# Power.net
KiCad netlist of a schematic drawn in Altium Designer
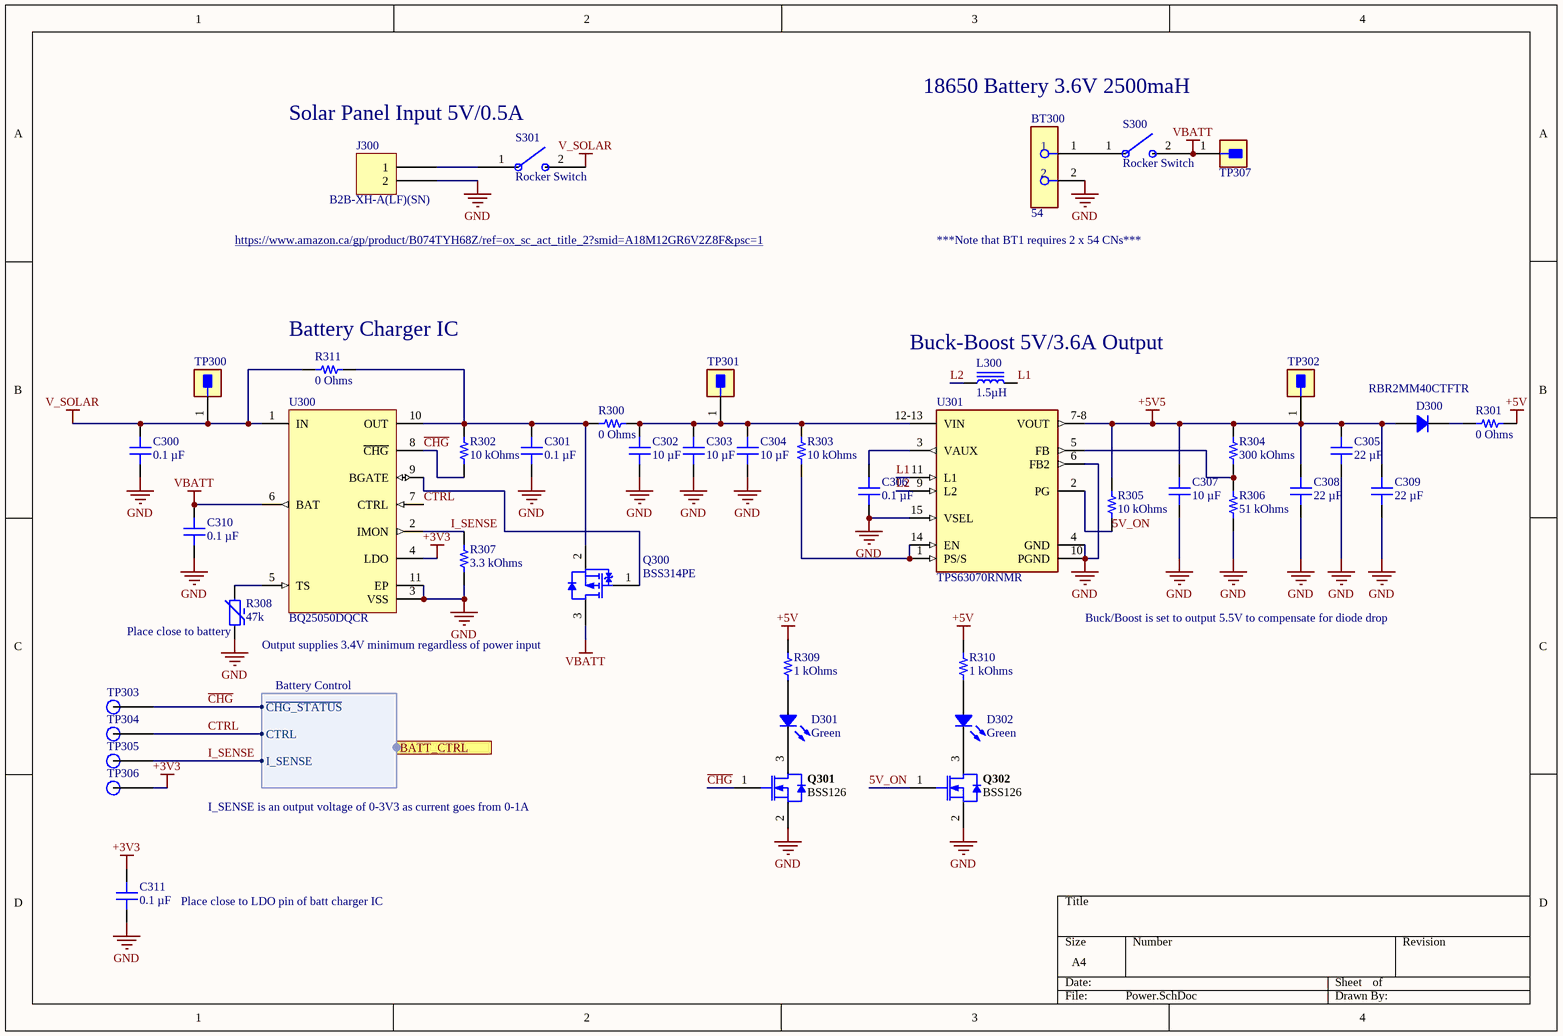
[diagram p0: Power.SchDoc]

(export (version "E")
  (design (tool "Eeschema 10.0.6"))
  (components
    (comp (ref "BT300")
      (value "54")
      (footprint "FP-54-MFG")
      (description "Cylindrical Battery Contacts, Clips, Holders & Springs 16-19mm PC BATTERY CLIP")
      (libsource (lib "Americas- Environmental Engineering Club- University of Victoria") (part "98815daf2f2c152b0c43f5ab9800df6"))
    )
    (comp (ref "C300")
      (value "0.1 µF")
      (footprint "CAP 0603_1608")
      (description "CAP CER 0.1UF 50V X7R 0603")
      (fields (field (name "PART NUMBER") "C0603C104K5RAC7411") (field (name "MANUFACTURER") "KEMET"))
      (libsource (lib "Celestial Altium Library - altium_library") (part "Capacitor"))
    )
    (comp (ref "C301")
      (value "0.1 µF")
      (footprint "CAP 0603_1608")
      (description "CAP CER 0.1UF 50V X7R 0603")
      (fields (field (name "PART NUMBER") "C0603C104K5RAC7411") (field (name "MANUFACTURER") "KEMET"))
      (libsource (lib "Celestial Altium Library - altium_library") (part "Capacitor"))
    )
    (comp (ref "C302")
      (value "10 µF")
      (footprint "CAP 0603_1608")
      (description "CAP CER 10UF 25V X5R 0603")
      (fields
        (field (name "PART NUMBER") "GRM188R61E106MA73J")
        (field (name "MANUFACTURER") "Murata Electronics")
      )
      (libsource (lib "Celestial Altium Library - altium_library") (part "Capacitor"))
    )
    (comp (ref "C303")
      (value "10 µF")
      (footprint "CAP 0603_1608")
      (description "CAP CER 10UF 25V X5R 0603")
      (fields
        (field (name "PART NUMBER") "GRM188R61E106MA73J")
        (field (name "MANUFACTURER") "Murata Electronics")
      )
      (libsource (lib "Celestial Altium Library - altium_library") (part "Capacitor"))
    )
    (comp (ref "C304")
      (value "10 µF")
      (footprint "CAP 0603_1608")
      (description "CAP CER 10UF 25V X5R 0603")
      (fields
        (field (name "PART NUMBER") "GRM188R61E106MA73J")
        (field (name "MANUFACTURER") "Murata Electronics")
      )
      (libsource (lib "Celestial Altium Library - altium_library") (part "Capacitor"))
    )
    (comp (ref "C305")
      (value "22 µF")
      (footprint "CAP 0805_2012")
      (description "CAP CER 22UF 16V X5R 0805")
      (fields
        (field (name "PART NUMBER") "CL21A226MOQNNNE")
        (field (name "MANUFACTURER") "Samsung Electro-Mechanics")
      )
      (libsource (lib "Celestial Altium Library - altium_library") (part "Capacitor"))
    )
    (comp (ref "C306")
      (value "0.1 µF")
      (footprint "CAP 0603_1608")
      (description "CAP CER 0.1UF 50V X7R 0603")
      (fields (field (name "PART NUMBER") "C0603C104K5RAC7411") (field (name "MANUFACTURER") "KEMET"))
      (libsource (lib "Celestial Altium Library - altium_library") (part "Capacitor"))
    )
    (comp (ref "C307")
      (value "10 µF")
      (footprint "CAP 0603_1608")
      (description "CAP CER 10UF 25V X5R 0603")
      (fields
        (field (name "PART NUMBER") "GRM188R61E106MA73J")
        (field (name "MANUFACTURER") "Murata Electronics")
      )
      (libsource (lib "Celestial Altium Library - altium_library") (part "Capacitor"))
    )
    (comp (ref "C308")
      (value "22 µF")
      (footprint "CAP 0805_2012")
      (description "CAP CER 22UF 16V X5R 0805")
      (fields
        (field (name "PART NUMBER") "CL21A226MOQNNNE")
        (field (name "MANUFACTURER") "Samsung Electro-Mechanics")
      )
      (libsource (lib "Celestial Altium Library - altium_library") (part "Capacitor"))
    )
    (comp (ref "C309")
      (value "22 µF")
      (footprint "CAP 0805_2012")
      (description "CAP CER 22UF 16V X5R 0805")
      (fields
        (field (name "PART NUMBER") "CL21A226MOQNNNE")
        (field (name "MANUFACTURER") "Samsung Electro-Mechanics")
      )
      (libsource (lib "Celestial Altium Library - altium_library") (part "Capacitor"))
    )
    (comp (ref "C310")
      (value "0.1 µF")
      (footprint "CAP 0603_1608")
      (description "CAP CER 0.1UF 50V X7R 0603")
      (fields (field (name "PART NUMBER") "C0603C104K5RAC7411") (field (name "MANUFACTURER") "KEMET"))
      (libsource (lib "Celestial Altium Library - altium_library") (part "Capacitor"))
    )
    (comp (ref "C311")
      (value "0.1 µF")
      (footprint "CAP 0603_1608")
      (description "CAP CER 0.1UF 50V X7R 0603")
      (fields (field (name "PART NUMBER") "C0603C104K5RAC7411") (field (name "MANUFACTURER") "KEMET"))
      (libsource (lib "Celestial Altium Library - altium_library") (part "Capacitor"))
    )
    (comp (ref "D300")
      (value "RBR2MM40CTFTR")
      (footprint "SOD123F")
      (description "DIODE (RECTIFIER FRD) 40V-VR 2A-")
      (fields (field (name "MANUFACTURER") "Rohm Semiconductor"))
      (libsource (lib "Celestial Altium Library - altium_library") (part "Diode"))
    )
    (comp (ref "D301")
      (value "Green")
      (footprint "LED 0603_1608 GREEN")
      (description "LED GREEN CLEAR 2SMD")
      (fields (field (name "PART NUMBER") "XZVGT53W-6") (field (name "MANUFACTURER") "SunLED"))
      (libsource (lib "Celestial Altium Library - altium_library") (part "LED"))
    )
    (comp (ref "D302")
      (value "Green")
      (footprint "LED 0603_1608 GREEN")
      (description "LED GREEN CLEAR 2SMD")
      (fields (field (name "PART NUMBER") "XZVGT53W-6") (field (name "MANUFACTURER") "SunLED"))
      (libsource (lib "Celestial Altium Library - altium_library") (part "LED"))
    )
    (comp (ref "J300")
      (value "B2B-XH-A(LF)(SN)")
      (footprint "JST XH B2B-XH-A")
      (description "CONN HEADER VERT 2POS 2.5MM")
      (fields (field (name "MANUFACTURER") "JST Sales America Inc."))
      (libsource (lib "Celestial Altium Library - altium_library") (part "2 Pin"))
    )
    (comp (ref "L300")
      (value "1.5µH")
      (footprint "IND 1008_2520")
      (description "FIXED IND 1.5UH 1.5A 70 MOHM SMD")
      (fields (field (name "PART NUMBER") "CVH252009-1R5M") (field (name "MANUFACTURER") "Bourns Inc."))
      (libsource (lib "Celestial Altium Library - altium_library") (part "Inductor"))
    )
    (comp (ref "Q300")
      (value "BSS314PE")
      (footprint "INF-PG-SOT23_N")
      (fields (field (name "MANUFACTURER") "Infineon"))
      (libsource (lib "Altium Content Vault") (part "INF-BSS3XXPE-PG-SOT23-3"))
    )
    (comp (ref "Q301")
      (value "BSS126")
      (footprint "INF-PG-SOT23_L")
      (fields (field (name "MANUFACTURER") "Infineon"))
      (libsource (lib "Altium Content Vault") (part "INF-NDMOS-GSD-3"))
    )
    (comp (ref "Q302")
      (value "BSS126")
      (footprint "INF-PG-SOT23_L")
      (fields (field (name "MANUFACTURER") "Infineon"))
      (libsource (lib "Altium Content Vault") (part "INF-NDMOS-GSD-3"))
    )
    (comp (ref "R300")
      (value "0 Ohms")
      (footprint "RES 0603_1608")
      (description "RES 0 OHM JUMPER 1/10W 0603")
      (fields (field (name "PART NUMBER") "PA0603-R-070RL") (field (name "MANUFACTURER") "Yageo"))
      (libsource (lib "Celestial Altium Library - altium_library") (part "Resistor"))
    )
    (comp (ref "R301")
      (value "0 Ohms")
      (footprint "RES 0603_1608")
      (description "RES 0 OHM JUMPER 1/10W 0603")
      (fields (field (name "PART NUMBER") "PA0603-R-070RL") (field (name "MANUFACTURER") "Yageo"))
      (libsource (lib "Celestial Altium Library - altium_library") (part "Resistor"))
    )
    (comp (ref "R302")
      (value "10 kOhms")
      (footprint "RES 0603_1608")
      (description "RES SMD 10K OHM 1% 1/10W 0603")
      (fields (field (name "PART NUMBER") "RT0603FRE0710KL") (field (name "MANUFACTURER") "Yageo"))
      (libsource (lib "Celestial Altium Library - altium_library") (part "Resistor"))
    )
    (comp (ref "R303")
      (value "10 kOhms")
      (footprint "RES 0603_1608")
      (description "RES SMD 10K OHM 1% 1/10W 0603")
      (fields (field (name "PART NUMBER") "RT0603FRE0710KL") (field (name "MANUFACTURER") "Yageo"))
      (libsource (lib "Celestial Altium Library - altium_library") (part "Resistor"))
    )
    (comp (ref "R304")
      (value "300 kOhms")
      (footprint "RES 0603_1608")
      (description "RES 300K OHM 1% 1/10W 0603")
      (fields (field (name "PART NUMBER") "RC0603FR-07300KL") (field (name "MANUFACTURER") "Yageo"))
      (libsource (lib "Celestial Altium Library - altium_library") (part "Resistor"))
    )
    (comp (ref "R305")
      (value "10 kOhms")
      (footprint "RES 0603_1608")
      (description "RES SMD 10K OHM 1% 1/10W 0603")
      (fields (field (name "PART NUMBER") "RT0603FRE0710KL") (field (name "MANUFACTURER") "Yageo"))
      (libsource (lib "Celestial Altium Library - altium_library") (part "Resistor"))
    )
    (comp (ref "R306")
      (value "51 kOhms")
      (footprint "RES 0603_1608")
      (description "RES SMD 51K OHM 1% 1/10W 0603")
      (fields (field (name "PART NUMBER") "CRCW060351K0FKEA") (field (name "MANUFACTURER") "Vishay Dale"))
      (libsource (lib "Celestial Altium Library - altium_library") (part "Resistor"))
    )
    (comp (ref "R307")
      (value "3.3 kOhms")
      (footprint "RES 0603_1608")
      (description "RES 3.3K OHM 1% 1/4W 0603")
      (fields
        (field (name "PART NUMBER") "CRGP0603F3K3")
        (field (name "MANUFACTURER") "TE Connectivity Passive Product")
      )
      (libsource (lib "Celestial Altium Library - altium_library") (part "Resistor"))
    )
    (comp (ref "R308")
      (value "47k")
      (footprint "NTC 0603_1608")
      (description "THERMISTOR NTC 47KOHM 4050K 0603")
      (fields
        (field (name "PART NUMBER") "NCP18WB473F10RB")
        (field (name "MANUFACTURER") "Murata Electronics")
      )
      (libsource (lib "Celestial Altium Library - altium_library") (part "Thermistor"))
    )
    (comp (ref "R309")
      (value "1 kOhms")
      (footprint "RES 0603_1608")
      (description "RES SMD 1K OHM 1% 1/10W 0603")
      (fields (field (name "PART NUMBER") "RT0603FRE071KL") (field (name "MANUFACTURER") "Yageo"))
      (libsource (lib "Celestial Altium Library - altium_library") (part "Resistor"))
    )
    (comp (ref "R310")
      (value "1 kOhms")
      (footprint "RES 0603_1608")
      (description "RES SMD 1K OHM 1% 1/10W 0603")
      (fields (field (name "PART NUMBER") "RT0603FRE071KL") (field (name "MANUFACTURER") "Yageo"))
      (libsource (lib "Celestial Altium Library - altium_library") (part "Resistor"))
    )
    (comp (ref "R311")
      (value "0 Ohms")
      (footprint "RES 0603_1608")
      (description "RES 0 OHM JUMPER 1/10W 0603")
      (fields (field (name "PART NUMBER") "PA0603-R-070RL") (field (name "MANUFACTURER") "Yageo"))
      (libsource (lib "Celestial Altium Library - altium_library") (part "Resistor"))
    )
    (comp (ref "S300")
      (value "Rocker Switch")
      (footprint "Rocker Switch-Footprint-1")
      (description "12mm x 18.5mm Rocker Switch 6A 250VAC")
      (libsource (lib "Americas- Environmental Engineering Club- University of Victoria") (part "Rocker Switch-Symbol-1"))
    )
    (comp (ref "S301")
      (value "Rocker Switch")
      (footprint "Rocker Switch-Footprint-1")
      (description "12mm x 18.5mm Rocker Switch 6A 250VAC")
      (libsource (lib "Americas- Environmental Engineering Club- University of Victoria") (part "Rocker Switch-Symbol-1"))
    )
    (comp (ref "TP300")
      (value "S2751-46R")
      (footprint "FP-S2751-46R-MFG")
      (description "Conn Test Point 1 POS Solder ST SMD 1 Port T/R")
      (libsource (lib "Americas- Environmental Engineering Club- University of Victoria") (part "dd45045ce8184df9e99e12baf3f412c"))
    )
    (comp (ref "TP301")
      (value "S2751-46R")
      (footprint "FP-S2751-46R-MFG")
      (description "Conn Test Point 1 POS Solder ST SMD 1 Port T/R")
      (libsource (lib "Americas- Environmental Engineering Club- University of Victoria") (part "dd45045ce8184df9e99e12baf3f412c"))
    )
    (comp (ref "TP302")
      (value "S2751-46R")
      (footprint "FP-S2751-46R-MFG")
      (description "Conn Test Point 1 POS Solder ST SMD 1 Port T/R")
      (libsource (lib "Americas- Environmental Engineering Club- University of Victoria") (part "dd45045ce8184df9e99e12baf3f412c"))
    )
    (comp (ref "TP303")
      (value "1.5mm Test Point")
      (footprint "1mm Test Point-Footprint-1")
      (description "1.5mm Test Point 0.75mm hole size")
      (libsource (lib "Americas- Environmental Engineering Club- University of Victoria") (part "1mm Test Point-Symbol-1"))
    )
    (comp (ref "TP304")
      (value "1.5mm Test Point")
      (footprint "1mm Test Point-Footprint-1")
      (description "1.5mm Test Point 0.75mm hole size")
      (libsource (lib "Americas- Environmental Engineering Club- University of Victoria") (part "1mm Test Point-Symbol-1"))
    )
    (comp (ref "TP305")
      (value "1.5mm Test Point")
      (footprint "1mm Test Point-Footprint-1")
      (description "1.5mm Test Point 0.75mm hole size")
      (libsource (lib "Americas- Environmental Engineering Club- University of Victoria") (part "1mm Test Point-Symbol-1"))
    )
    (comp (ref "TP306")
      (value "1.5mm Test Point")
      (footprint "1mm Test Point-Footprint-1")
      (description "1.5mm Test Point 0.75mm hole size")
      (libsource (lib "Americas- Environmental Engineering Club- University of Victoria") (part "1mm Test Point-Symbol-1"))
    )
    (comp (ref "TP307")
      (value "S2751-46R")
      (footprint "FP-S2751-46R-MFG")
      (description "Conn Test Point 1 POS Solder ST SMD 1 Port T/R")
      (libsource (lib "") (part "dd45045ce8184df9e99e12baf3f412c_1"))
    )
    (comp (ref "U300")
      (value "BQ25050DQCR")
      (footprint "DQC0010A")
      (fields (field (name "MANUFACTURER") "Texas Instruments"))
      (libsource (lib "Altium Content Vault") (part "TI-BQ25050DQC10-2400X840TP"))
    )
    (comp (ref "U301")
      (value "TPS63070RNMR")
      (footprint "FP-RNM0015A-MFG")
      (description "IC REG BCK BST ADJ 3.6A 15VQFN")
      (libsource (lib "Altium Content Vault") (part "a4d5b1e6901c8533e317c4aea8f1b15"))
    )
  )
  (nets
    (net (code "3") (name "+3V3") (class "Default")
      (node (ref "C311") (pin "2") (pinfunction "2_2") (pintype "passive"))
      (node (ref "TP306") (pin "1") (pinfunction "1_1") (pintype "passive"))
      (node (ref "U300") (pin "4") (pinfunction "LDO_4") (pintype "power_in"))
    )
    (net (code "4") (name "+5V") (class "Default")
      (node (ref "R301") (pin "2") (pinfunction "2_2") (pintype "passive"))
      (node (ref "R309") (pin "2") (pinfunction "2_2") (pintype "passive"))
      (node (ref "R310") (pin "2") (pinfunction "2_2") (pintype "passive"))
    )
    (net (code "5") (name "+5V5") (class "Default")
      (node (ref "C305") (pin "2") (pinfunction "2_2") (pintype "passive"))
      (node (ref "C307") (pin "2") (pinfunction "2_2") (pintype "passive"))
      (node (ref "C308") (pin "2") (pinfunction "2_2") (pintype "passive"))
      (node (ref "C309") (pin "2") (pinfunction "2_2") (pintype "passive"))
      (node (ref "D300") (pin "1") (pinfunction "1_1") (pintype "passive"))
      (node (ref "R304") (pin "2") (pinfunction "2_2") (pintype "passive"))
      (node (ref "R305") (pin "2") (pinfunction "2_2") (pintype "passive"))
      (node (ref "TP302") (pin "1") (pinfunction "1_1") (pintype "passive"))
      (node (ref "U301") (pin "7-8") (pinfunction "VOUT_7-8") (pintype "output"))
    )
    (net (code "6") (name "/5V_ON") (class "Default")
      (node (ref "Q302") (pin "1") (pinfunction "GATE_1") (pintype "passive"))
      (node (ref "R305") (pin "1") (pinfunction "1_1") (pintype "passive"))
      (node (ref "U301") (pin "2") (pinfunction "PG_2") (pintype "open_collector"))
    )
    (net (code "7") (name "/CTRL") (class "Default")
      (node (ref "TP304") (pin "1") (pinfunction "1_1") (pintype "passive"))
      (node (ref "U300") (pin "7") (pinfunction "CTRL_7") (pintype "input"))
    )
    (net (code "8") (name "/I_SENSE") (class "Default")
      (node (ref "R307") (pin "2") (pinfunction "2_2") (pintype "passive"))
      (node (ref "TP305") (pin "1") (pinfunction "1_1") (pintype "passive"))
      (node (ref "U300") (pin "2") (pinfunction "IMON_2") (pintype "output"))
    )
    (net (code "9") (name "/L1") (class "Default")
      (node (ref "L300") (pin "2") (pinfunction "2_2") (pintype "passive"))
      (node (ref "U301") (pin "11") (pinfunction "L1_11") (pintype "input"))
    )
    (net (code "10") (name "/L2") (class "Default")
      (node (ref "L300") (pin "1") (pinfunction "1_1") (pintype "passive"))
      (node (ref "U301") (pin "9") (pinfunction "L2_9") (pintype "input"))
    )
    (net (code "12") (name "/~{CHG}") (class "Default")
      (node (ref "Q301") (pin "1") (pinfunction "GATE_1") (pintype "passive"))
      (node (ref "R302") (pin "1") (pinfunction "1_1") (pintype "passive"))
      (node (ref "TP303") (pin "1") (pinfunction "1_1") (pintype "passive"))
      (node (ref "U300") (pin "8") (pinfunction "~{CHG}_8") (pintype "tri_state"))
    )
    (net (code "13") (name "GND") (class "Default")
      (node (ref "BT300") (pin "2") (pinfunction "2_2") (pintype "power_in"))
      (node (ref "C300") (pin "1") (pinfunction "1_1") (pintype "passive"))
      (node (ref "C301") (pin "1") (pinfunction "1_1") (pintype "passive"))
      (node (ref "C302") (pin "1") (pinfunction "1_1") (pintype "passive"))
      (node (ref "C303") (pin "1") (pinfunction "1_1") (pintype "passive"))
      (node (ref "C304") (pin "1") (pinfunction "1_1") (pintype "passive"))
      (node (ref "C305") (pin "1") (pinfunction "1_1") (pintype "passive"))
      (node (ref "C306") (pin "1") (pinfunction "1_1") (pintype "passive"))
      (node (ref "C307") (pin "1") (pinfunction "1_1") (pintype "passive"))
      (node (ref "C308") (pin "1") (pinfunction "1_1") (pintype "passive"))
      (node (ref "C309") (pin "1") (pinfunction "1_1") (pintype "passive"))
      (node (ref "C310") (pin "1") (pinfunction "1_1") (pintype "passive"))
      (node (ref "C311") (pin "1") (pinfunction "1_1") (pintype "passive"))
      (node (ref "J300") (pin "2") (pinfunction "2_2") (pintype "passive"))
      (node (ref "Q301") (pin "2") (pinfunction "SOURCE_2") (pintype "passive"))
      (node (ref "Q302") (pin "2") (pinfunction "SOURCE_2") (pintype "passive"))
      (node (ref "R306") (pin "1") (pinfunction "1_1") (pintype "passive"))
      (node (ref "R307") (pin "1") (pinfunction "1_1") (pintype "passive"))
      (node (ref "R308") (pin "1") (pinfunction "1_1") (pintype "passive"))
      (node (ref "U300") (pin "11") (pinfunction "EP_11") (pintype "power_in"))
      (node (ref "U300") (pin "3") (pinfunction "VSS_3") (pintype "power_in"))
      (node (ref "U301") (pin "10") (pinfunction "PGND_10") (pintype "power_in"))
      (node (ref "U301") (pin "15") (pinfunction "VSEL_15") (pintype "input"))
      (node (ref "U301") (pin "4") (pinfunction "GND_4") (pintype "power_in"))
      (node (ref "U301") (pin "6") (pinfunction "FB2_6") (pintype "output"))
    )
    (net (code "14") (name "Net-(BT300-Pad1)") (class "Default")
      (node (ref "BT300") (pin "1") (pinfunction "1_1") (pintype "power_in"))
      (node (ref "S300") (pin "1") (pinfunction "1_1") (pintype "passive"))
    )
    (net (code "15") (name "Net-(D300-Pad2)") (class "Default")
      (node (ref "D300") (pin "2") (pinfunction "2_2") (pintype "passive"))
      (node (ref "R301") (pin "1") (pinfunction "1_1") (pintype "passive"))
    )
    (net (code "16") (name "Net-(D301-Pad1)") (class "Default")
      (node (ref "D301") (pin "1") (pinfunction "1_1") (pintype "passive"))
      (node (ref "R309") (pin "1") (pinfunction "1_1") (pintype "passive"))
    )
    (net (code "17") (name "Net-(D302-Pad1)") (class "Default")
      (node (ref "D302") (pin "1") (pinfunction "1_1") (pintype "passive"))
      (node (ref "R310") (pin "1") (pinfunction "1_1") (pintype "passive"))
    )
    (net (code "18") (name "Net-(J300-Pad1)") (class "Default")
      (node (ref "J300") (pin "1") (pinfunction "1_1") (pintype "passive"))
      (node (ref "S301") (pin "1") (pinfunction "1_1") (pintype "passive"))
    )
    (net (code "19") (name "Net-(Q300-GATE)") (class "Default")
      (node (ref "Q300") (pin "1") (pinfunction "GATE_1") (pintype "passive"))
      (node (ref "U300") (pin "9") (pinfunction "BGATE_9") (pintype "bidirectional"))
    )
    (net (code "20") (name "Net-(Q300-SOURCE)") (class "Default")
      (node (ref "C301") (pin "2") (pinfunction "2_2") (pintype "passive"))
      (node (ref "Q300") (pin "2") (pinfunction "SOURCE_2") (pintype "passive"))
      (node (ref "R300") (pin "1") (pinfunction "1_1") (pintype "passive"))
      (node (ref "R302") (pin "2") (pinfunction "2_2") (pintype "passive"))
      (node (ref "R311") (pin "2") (pinfunction "2_2") (pintype "passive"))
      (node (ref "U300") (pin "10") (pinfunction "OUT_10") (pintype "power_in"))
    )
    (net (code "21") (name "Net-(Q301-DRAIN)") (class "Default")
      (node (ref "D301") (pin "2") (pinfunction "2_2") (pintype "passive"))
      (node (ref "Q301") (pin "3") (pinfunction "DRAIN_3") (pintype "passive"))
    )
    (net (code "22") (name "Net-(Q302-DRAIN)") (class "Default")
      (node (ref "D302") (pin "2") (pinfunction "2_2") (pintype "passive"))
      (node (ref "Q302") (pin "3") (pinfunction "DRAIN_3") (pintype "passive"))
    )
    (net (code "23") (name "Net-(U300-TS)") (class "Default")
      (node (ref "R308") (pin "2") (pinfunction "2_2") (pintype "passive"))
      (node (ref "U300") (pin "5") (pinfunction "TS_5") (pintype "input"))
    )
    (net (code "24") (name "Net-(U301-EN)") (class "Default")
      (node (ref "R303") (pin "1") (pinfunction "1_1") (pintype "passive"))
      (node (ref "U301") (pin "1") (pinfunction "PS/S_1") (pintype "input"))
      (node (ref "U301") (pin "14") (pinfunction "EN_14") (pintype "input"))
    )
    (net (code "25") (name "Net-(U301-FB)") (class "Default")
      (node (ref "R304") (pin "1") (pinfunction "1_1") (pintype "passive"))
      (node (ref "R306") (pin "2") (pinfunction "2_2") (pintype "passive"))
      (node (ref "U301") (pin "5") (pinfunction "FB_5") (pintype "output"))
    )
    (net (code "26") (name "Net-(U301-VAUX)") (class "Default")
      (node (ref "C306") (pin "2") (pinfunction "2_2") (pintype "passive"))
      (node (ref "U301") (pin "3") (pinfunction "VAUX_3") (pintype "output"))
    )
    (net (code "27") (name "Net-(U301-VIN)") (class "Default")
      (node (ref "C302") (pin "2") (pinfunction "2_2") (pintype "passive"))
      (node (ref "C303") (pin "2") (pinfunction "2_2") (pintype "passive"))
      (node (ref "C304") (pin "2") (pinfunction "2_2") (pintype "passive"))
      (node (ref "R300") (pin "2") (pinfunction "2_2") (pintype "passive"))
      (node (ref "R303") (pin "2") (pinfunction "2_2") (pintype "passive"))
      (node (ref "TP301") (pin "1") (pinfunction "1_1") (pintype "passive"))
      (node (ref "U301") (pin "12-13") (pinfunction "VIN_12-13") (pintype "power_in"))
    )
    (net (code "28") (name "VBATT") (class "Default")
      (node (ref "C310") (pin "2") (pinfunction "2_2") (pintype "passive"))
      (node (ref "Q300") (pin "3") (pinfunction "DRAIN_3") (pintype "passive"))
      (node (ref "S300") (pin "2") (pinfunction "2_2") (pintype "passive"))
      (node (ref "TP307") (pin "1") (pinfunction "1_1") (pintype "passive"))
      (node (ref "U300") (pin "6") (pinfunction "BAT_6") (pintype "output"))
    )
    (net (code "29") (name "V_SOLAR") (class "Default")
      (node (ref "C300") (pin "2") (pinfunction "2_2") (pintype "passive"))
      (node (ref "R311") (pin "1") (pinfunction "1_1") (pintype "passive"))
      (node (ref "S301") (pin "2") (pinfunction "2_2") (pintype "passive"))
      (node (ref "TP300") (pin "1") (pinfunction "1_1") (pintype "passive"))
      (node (ref "U300") (pin "1") (pinfunction "IN_1") (pintype "power_in"))
    )
  )
)
